# VC8Evrs.net
KiCad netlist of a schematic drawn in EAGLE
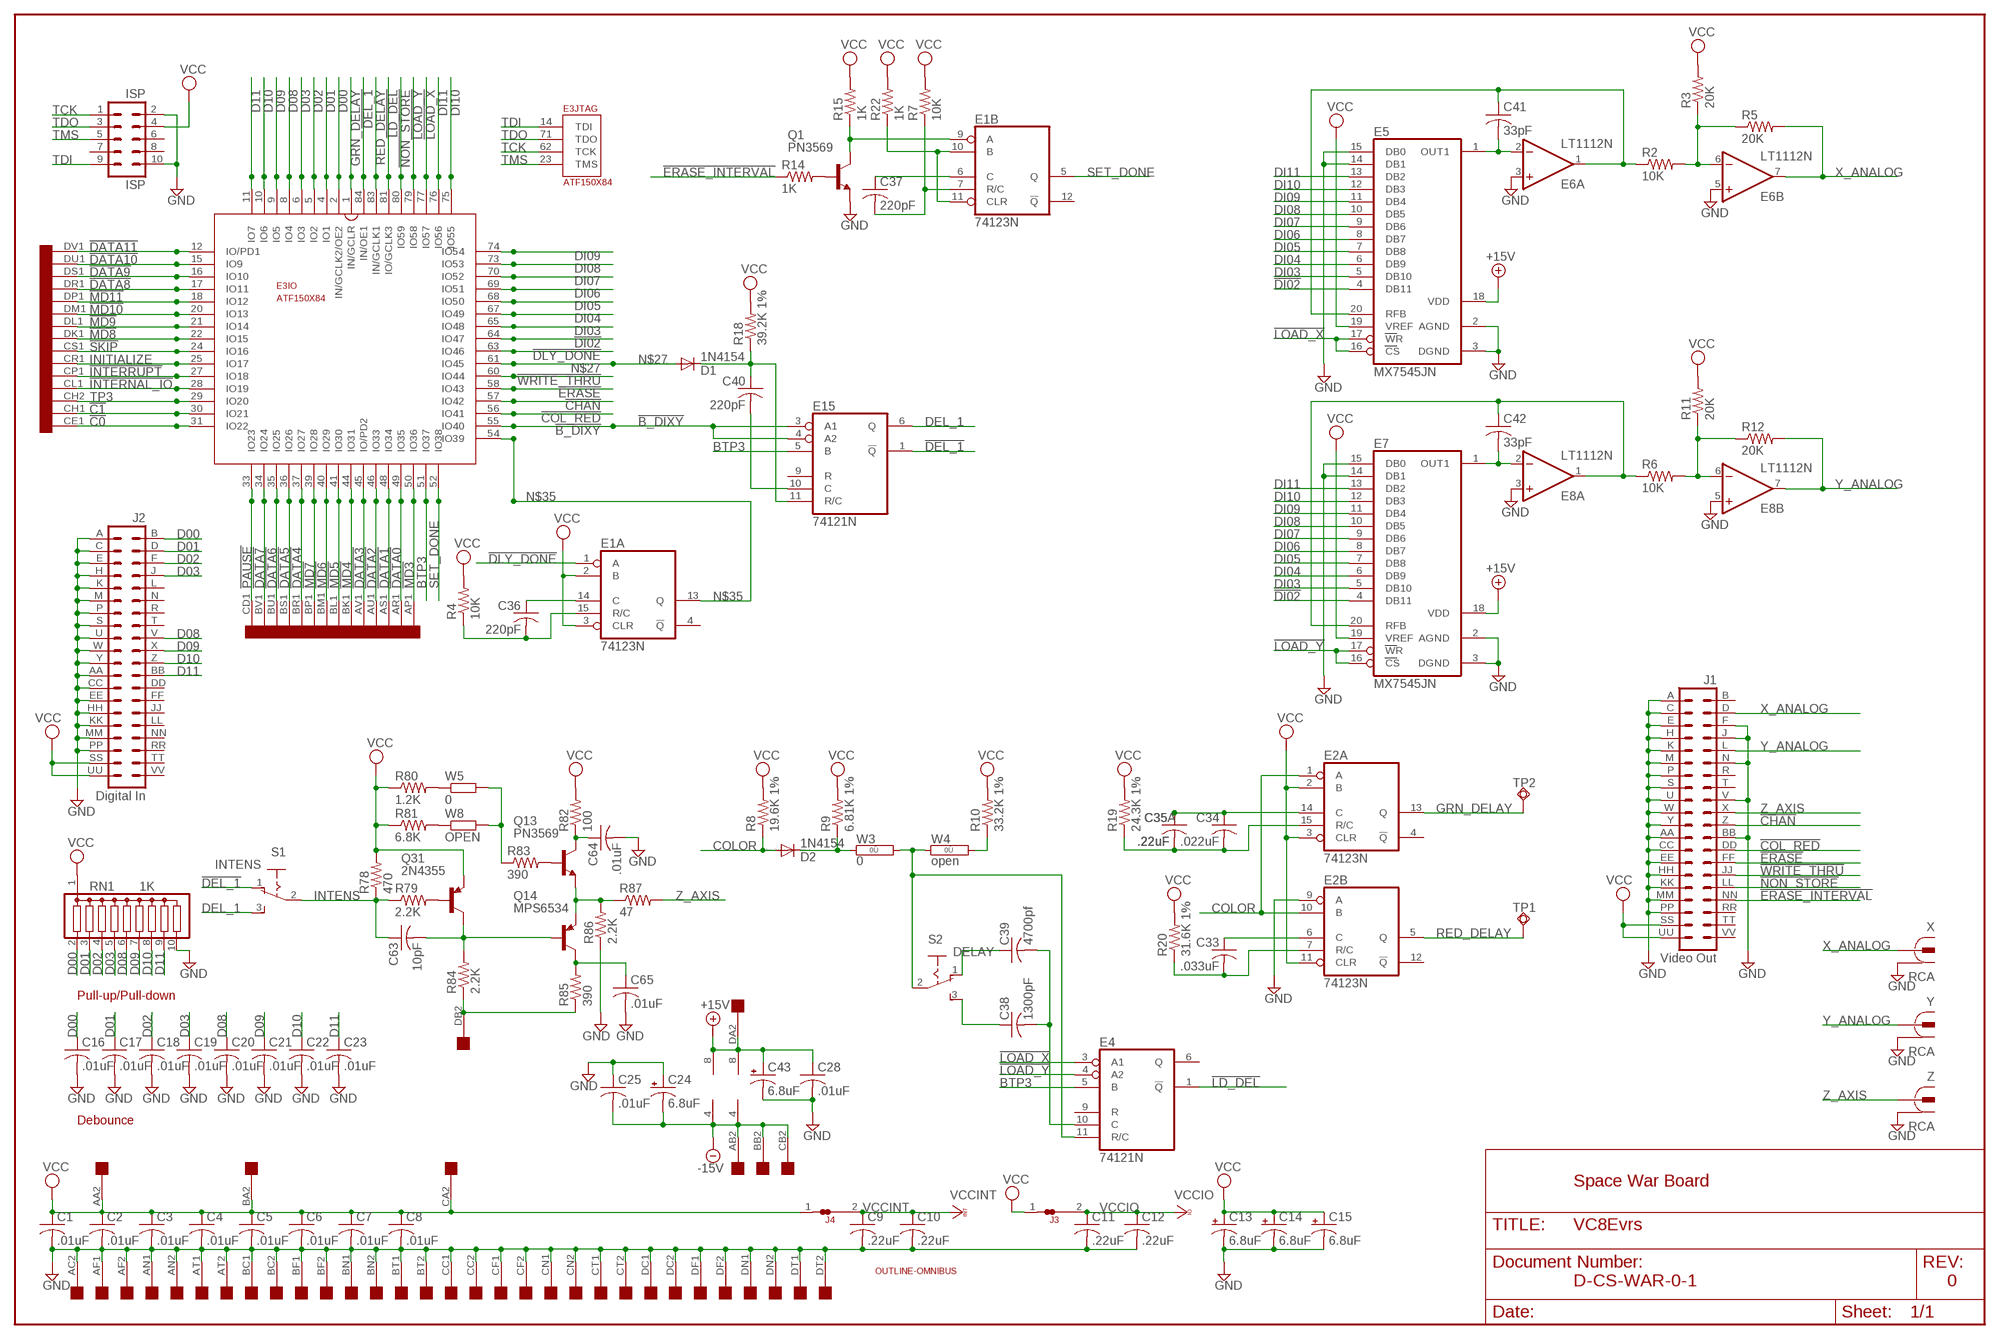
[diagram p0: schematic, sheet 1]

(export (version "E")
  (design (tool "Eeschema 10.0.6"))
  (components
    (comp (ref "C1")
      (value ".01uF")
      (footprint "eagle-import:C063-025X075")
      (libsource (lib "eagle-import") (part "C-US"))
    )
    (comp (ref "C2")
      (value ".01uF")
      (footprint "eagle-import:C063-025X075")
      (libsource (lib "eagle-import") (part "C-US"))
    )
    (comp (ref "C3")
      (value ".01uF")
      (footprint "eagle-import:C063-025X075")
      (libsource (lib "eagle-import") (part "C-US"))
    )
    (comp (ref "C4")
      (value ".01uF")
      (footprint "eagle-import:C063-025X075")
      (libsource (lib "eagle-import") (part "C-US"))
    )
    (comp (ref "C5")
      (value ".01uF")
      (footprint "eagle-import:C063-025X075")
      (libsource (lib "eagle-import") (part "C-US"))
    )
    (comp (ref "C6")
      (value ".01uF")
      (footprint "eagle-import:C063-025X075")
      (libsource (lib "eagle-import") (part "C-US"))
    )
    (comp (ref "C7")
      (value ".01uF")
      (footprint "eagle-import:C063-025X075")
      (libsource (lib "eagle-import") (part "C-US"))
    )
    (comp (ref "C8")
      (value ".01uF")
      (footprint "eagle-import:C063-025X075")
      (libsource (lib "eagle-import") (part "C-US"))
    )
    (comp (ref "C9")
      (value ".22uF")
      (footprint "eagle-import:C063-025X075")
      (libsource (lib "eagle-import") (part "C-US"))
    )
    (comp (ref "C10")
      (value ".22uF")
      (footprint "eagle-import:C063-025X075")
      (libsource (lib "eagle-import") (part "C-US"))
    )
    (comp (ref "C11")
      (value ".22uF")
      (footprint "eagle-import:C063-025X075")
      (libsource (lib "eagle-import") (part "C-US"))
    )
    (comp (ref "C12")
      (value ".22uF")
      (footprint "eagle-import:C063-025X075")
      (libsource (lib "eagle-import") (part "C-US"))
    )
    (comp (ref "C13")
      (value "6.8uF")
      (footprint "eagle-import:E12-8")
      (libsource (lib "eagle-import") (part "CPOL-USE20-8AXIAL"))
    )
    (comp (ref "C14")
      (value "6.8uF")
      (footprint "eagle-import:E12-8")
      (libsource (lib "eagle-import") (part "CPOL-USE20-8AXIAL"))
    )
    (comp (ref "C15")
      (value "6.8uF")
      (footprint "eagle-import:E12-8")
      (libsource (lib "eagle-import") (part "CPOL-USE20-8AXIAL"))
    )
    (comp (ref "C16")
      (value ".01uF")
      (footprint "eagle-import:C063-025X075")
      (libsource (lib "eagle-import") (part "C-US"))
    )
    (comp (ref "C17")
      (value ".01uF")
      (footprint "eagle-import:C063-025X075")
      (libsource (lib "eagle-import") (part "C-US"))
    )
    (comp (ref "C18")
      (value ".01uF")
      (footprint "eagle-import:C063-025X075")
      (libsource (lib "eagle-import") (part "C-US"))
    )
    (comp (ref "C19")
      (value ".01uF")
      (footprint "eagle-import:C063-025X075")
      (libsource (lib "eagle-import") (part "C-US"))
    )
    (comp (ref "C20")
      (value ".01uF")
      (footprint "eagle-import:C063-025X075")
      (libsource (lib "eagle-import") (part "C-US"))
    )
    (comp (ref "C21")
      (value ".01uF")
      (footprint "eagle-import:C063-025X075")
      (libsource (lib "eagle-import") (part "C-US"))
    )
    (comp (ref "C22")
      (value ".01uF")
      (footprint "eagle-import:C063-025X075")
      (libsource (lib "eagle-import") (part "C-US"))
    )
    (comp (ref "C23")
      (value ".01uF")
      (footprint "eagle-import:C063-025X075")
      (libsource (lib "eagle-import") (part "C-US"))
    )
    (comp (ref "C24")
      (value "6.8uF")
      (footprint "eagle-import:E12-8")
      (libsource (lib "eagle-import") (part "CPOL-USE20-8AXIAL"))
    )
    (comp (ref "C25")
      (value ".01uF")
      (footprint "eagle-import:C063-025X075")
      (libsource (lib "eagle-import") (part "C-US"))
    )
    (comp (ref "C28")
      (value ".01uF")
      (footprint "eagle-import:C063-025X075")
      (libsource (lib "eagle-import") (part "C-US"))
    )
    (comp (ref "C33")
      (value ".033uF")
      (footprint "eagle-import:C102-043X133")
      (libsource (lib "eagle-import") (part "C-US102-043X133"))
    )
    (comp (ref "C34")
      (value ".022uF")
      (footprint "eagle-import:C102-043X133")
      (libsource (lib "eagle-import") (part "C-US102-043X133"))
    )
    (comp (ref "C35")
      (value ".22uF")
      (footprint "eagle-import:C050-025X075")
      (libsource (lib "eagle-import") (part "C-US050-025X075"))
    )
    (comp (ref "C35A")
      (value ".22uF")
      (footprint "eagle-import:C102-043X133")
      (libsource (lib "eagle-import") (part "C-US102-043X133"))
    )
    (comp (ref "C36")
      (value "220pF")
      (footprint "eagle-import:C063-025X075")
      (libsource (lib "eagle-import") (part "C-US"))
    )
    (comp (ref "C37")
      (value "220pF")
      (footprint "eagle-import:C063-025X075")
      (libsource (lib "eagle-import") (part "C-US"))
    )
    (comp (ref "C38")
      (value "1300pF")
      (footprint "eagle-import:C150-054X183")
      (libsource (lib "eagle-import") (part "C-US150-054X183"))
    )
    (comp (ref "C39")
      (value "4700pf")
      (footprint "eagle-import:C102-043X133")
      (libsource (lib "eagle-import") (part "C-US102-043X133"))
    )
    (comp (ref "C40")
      (value "220pF")
      (footprint "eagle-import:C063-025X075")
      (libsource (lib "eagle-import") (part "C-US"))
    )
    (comp (ref "C41")
      (value "33pF")
      (footprint "eagle-import:C063-025X075")
      (libsource (lib "eagle-import") (part "C-US"))
    )
    (comp (ref "C42")
      (value "33pF")
      (footprint "eagle-import:C063-025X075")
      (libsource (lib "eagle-import") (part "C-US"))
    )
    (comp (ref "C43")
      (value "6.8uF")
      (footprint "eagle-import:E12-8")
      (libsource (lib "eagle-import") (part "CPOL-USE20-8AXIAL"))
    )
    (comp (ref "C63")
      (value "10pF")
      (footprint "eagle-import:C063-025X075")
      (libsource (lib "eagle-import") (part "C-US"))
    )
    (comp (ref "C64")
      (value ".01uF")
      (footprint "eagle-import:C063-025X075")
      (libsource (lib "eagle-import") (part "C-US"))
    )
    (comp (ref "C65")
      (value ".01uF")
      (footprint "eagle-import:C063-025X075")
      (libsource (lib "eagle-import") (part "C-US"))
    )
    (comp (ref "D1")
      (value "1N4154")
      (footprint "eagle-import:DO35-10")
      (libsource (lib "eagle-import") (part "DIODE-DO35-10"))
    )
    (comp (ref "D2")
      (value "1N4154")
      (footprint "eagle-import:DO35-10")
      (libsource (lib "eagle-import") (part "DIODE-DO35-10"))
    )
    (comp (ref "E1")
      (value "74123N")
      (footprint "eagle-import:DIL16")
      (libsource (lib "eagle-import") (part "74123N"))
    )
    (comp (ref "E2")
      (value "74123N")
      (footprint "eagle-import:DIL16")
      (libsource (lib "eagle-import") (part "74123N"))
    )
    (comp (ref "E3")
      (value "ATF150X84")
      (footprint "eagle-import:S84")
      (libsource (lib "eagle-import") (part "ATF150X84"))
    )
    (comp (ref "E4")
      (value "74121N")
      (footprint "eagle-import:DIL14")
      (libsource (lib "eagle-import") (part "74121N"))
    )
    (comp (ref "E5")
      (value "MX7545JN")
      (footprint "eagle-import:DIL20")
      (fields (field (name "MPN") "MX7545JN+"))
      (libsource (lib "eagle-import") (part "MX7545JN"))
    )
    (comp (ref "E6")
      (value "LT1112N")
      (footprint "eagle-import:DIL08")
      (libsource (lib "eagle-import") (part "1458NLM"))
    )
    (comp (ref "E7")
      (value "MX7545JN")
      (footprint "eagle-import:DIL20")
      (fields (field (name "MPN") "MX7545JN+"))
      (libsource (lib "eagle-import") (part "MX7545JN"))
    )
    (comp (ref "E8")
      (value "LT1112N")
      (footprint "eagle-import:DIL08")
      (libsource (lib "eagle-import") (part "1458NLM"))
    )
    (comp (ref "E15")
      (value "74121N")
      (footprint "eagle-import:DIL14")
      (libsource (lib "eagle-import") (part "74121N"))
    )
    (comp (ref "ISP")
      (value "ISP")
      (footprint "eagle-import:ML10")
      (libsource (lib "eagle-import") (part "ML10"))
    )
    (comp (ref "J1")
      (value "Video Out")
      (footprint "eagle-import:DEC40PINH")
      (libsource (lib "eagle-import") (part "DEC40PINH"))
    )
    (comp (ref "J2")
      (value "Digital In")
      (footprint "eagle-import:DEC40PINH")
      (libsource (lib "eagle-import") (part "DEC40PINH"))
    )
    (comp (ref "J3")
      (value "JUMPER-NC1")
      (footprint "eagle-import:NC1")
      (libsource (lib "eagle-import") (part "JUMPER-NC1"))
    )
    (comp (ref "J4")
      (value "JUMPER-NC1")
      (footprint "eagle-import:NC1")
      (libsource (lib "eagle-import") (part "JUMPER-NC1"))
    )
    (comp (ref "OMNIBUS")
      (value "QUAD")
      (footprint "eagle-import:EDGE-CON8")
      (libsource (lib "eagle-import") (part "QUAD"))
    )
    (comp (ref "Q1")
      (value "PN3569")
      (footprint "eagle-import:TO18-")
      (libsource (lib "eagle-import") (part "-NPN-TO18-"))
    )
    (comp (ref "Q13")
      (value "PN3569")
      (footprint "eagle-import:TO5")
      (libsource (lib "eagle-import") (part "-NPN-TO5"))
    )
    (comp (ref "Q14")
      (value "MPS6534")
      (footprint "eagle-import:TO5")
      (libsource (lib "eagle-import") (part "-PNP-TO5"))
    )
    (comp (ref "Q31")
      (value "2N4355")
      (footprint "eagle-import:TO5")
      (libsource (lib "eagle-import") (part "-PNP-TO5"))
    )
    (comp (ref "R2")
      (value "10K")
      (footprint "eagle-import:0207_10")
      (libsource (lib "eagle-import") (part "R-US_0207/10"))
    )
    (comp (ref "R3")
      (value "20K")
      (footprint "eagle-import:0207_10")
      (libsource (lib "eagle-import") (part "R-US_0207/10"))
    )
    (comp (ref "R4")
      (value "10K")
      (footprint "eagle-import:0207_10")
      (libsource (lib "eagle-import") (part "R-US_0207/10"))
    )
    (comp (ref "R5")
      (value "20K")
      (footprint "eagle-import:0207_10")
      (libsource (lib "eagle-import") (part "R-US_0207/10"))
    )
    (comp (ref "R6")
      (value "10K")
      (footprint "eagle-import:0207_10")
      (libsource (lib "eagle-import") (part "R-US_0207/10"))
    )
    (comp (ref "R7")
      (value "10K")
      (footprint "eagle-import:0207_10")
      (libsource (lib "eagle-import") (part "R-US_0207/10"))
    )
    (comp (ref "R8")
      (value "19.6K 1%")
      (footprint "eagle-import:0207_15")
      (libsource (lib "eagle-import") (part "R-US_0207/15"))
    )
    (comp (ref "R9")
      (value "6.81K 1%")
      (footprint "eagle-import:0207_15")
      (libsource (lib "eagle-import") (part "R-US_0207/15"))
    )
    (comp (ref "R10")
      (value "33.2K 1%")
      (footprint "eagle-import:0207_15")
      (libsource (lib "eagle-import") (part "R-US_0207/15"))
    )
    (comp (ref "R11")
      (value "20K")
      (footprint "eagle-import:0207_10")
      (libsource (lib "eagle-import") (part "R-US_0207/10"))
    )
    (comp (ref "R12")
      (value "20K")
      (footprint "eagle-import:0207_10")
      (libsource (lib "eagle-import") (part "R-US_0207/10"))
    )
    (comp (ref "R14")
      (value "1K")
      (footprint "eagle-import:0207_10")
      (libsource (lib "eagle-import") (part "R-US_0207/10"))
    )
    (comp (ref "R15")
      (value "1K")
      (footprint "eagle-import:0207_10")
      (libsource (lib "eagle-import") (part "R-US_0207/10"))
    )
    (comp (ref "R18")
      (value "39.2K 1%")
      (footprint "eagle-import:0207_15")
      (libsource (lib "eagle-import") (part "R-US_0207/15"))
    )
    (comp (ref "R19")
      (value "24.3K 1%")
      (footprint "eagle-import:0207_15")
      (libsource (lib "eagle-import") (part "R-US_0207/15"))
    )
    (comp (ref "R20")
      (value "31.6K 1%")
      (footprint "eagle-import:0207_15")
      (libsource (lib "eagle-import") (part "R-US_0207/15"))
    )
    (comp (ref "R22")
      (value "1K")
      (footprint "eagle-import:0207_10")
      (libsource (lib "eagle-import") (part "R-US_0207/10"))
    )
    (comp (ref "R78")
      (value "470")
      (footprint "eagle-import:0207_10")
      (libsource (lib "eagle-import") (part "R-US_0207/10"))
    )
    (comp (ref "R79")
      (value "2.2K")
      (footprint "eagle-import:0207_10")
      (libsource (lib "eagle-import") (part "R-US_0207/10"))
    )
    (comp (ref "R80")
      (value "1.2K")
      (footprint "eagle-import:0207_10")
      (libsource (lib "eagle-import") (part "R-US_0207/10"))
    )
    (comp (ref "R81")
      (value "6.8K")
      (footprint "eagle-import:0207_10")
      (libsource (lib "eagle-import") (part "R-US_0207/10"))
    )
    (comp (ref "R82")
      (value "100")
      (footprint "eagle-import:0207_10")
      (libsource (lib "eagle-import") (part "R-US_0207/10"))
    )
    (comp (ref "R83")
      (value "390")
      (footprint "eagle-import:0207_10")
      (libsource (lib "eagle-import") (part "R-US_0207/10"))
    )
    (comp (ref "R84")
      (value "2.2K")
      (footprint "eagle-import:0207_10")
      (libsource (lib "eagle-import") (part "R-US_0207/10"))
    )
    (comp (ref "R85")
      (value "390")
      (footprint "eagle-import:0207_10")
      (libsource (lib "eagle-import") (part "R-US_0207/10"))
    )
    (comp (ref "R86")
      (value "2.2K")
      (footprint "eagle-import:0207_10")
      (libsource (lib "eagle-import") (part "R-US_0207/10"))
    )
    (comp (ref "R87")
      (value "47")
      (footprint "eagle-import:0207_10")
      (libsource (lib "eagle-import") (part "R-US_0207/10"))
    )
    (comp (ref "RN1")
      (value "1K")
      (footprint "eagle-import:SIL10")
      (libsource (lib "eagle-import") (part "G09R"))
    )
    (comp (ref "S1")
      (value "INTENS")
      (footprint "eagle-import:M251")
      (libsource (lib "eagle-import") (part "M251"))
    )
    (comp (ref "S2")
      (value "DELAY")
      (footprint "eagle-import:M251")
      (libsource (lib "eagle-import") (part "M251"))
    )
    (comp (ref "TP1")
      (value "TPSQPAD1-17")
      (footprint "eagle-import:P1-17")
      (libsource (lib "eagle-import") (part "TPSQPAD1-17"))
    )
    (comp (ref "TP2")
      (value "TPSQPAD1-17")
      (footprint "eagle-import:P1-17")
      (libsource (lib "eagle-import") (part "TPSQPAD1-17"))
    )
    (comp (ref "U$1")
      (value "OUTLINE-OMNIBUS")
      (footprint "eagle-import:OMNIBUS")
      (libsource (lib "eagle-import") (part "OUTLINE-OMNIBUS"))
    )
    (comp (ref "W3")
      (value "0")
      (footprint "eagle-import:0R_10")
      (libsource (lib "eagle-import") (part "0R"))
    )
    (comp (ref "W4")
      (value "open")
      (footprint "eagle-import:0R_10")
      (libsource (lib "eagle-import") (part "0R"))
    )
    (comp (ref "W5")
      (value "0")
      (footprint "eagle-import:0207_10")
      (libsource (lib "eagle-import") (part "R-EU_0207/10"))
    )
    (comp (ref "W8")
      (value "OPEN")
      (footprint "eagle-import:0207_10")
      (libsource (lib "eagle-import") (part "R-EU_0207/10"))
    )
    (comp (ref "X")
      (value "RCA")
      (footprint "eagle-import:RCA")
      (libsource (lib "eagle-import") (part "RCA"))
    )
    (comp (ref "Y")
      (value "RCA")
      (footprint "eagle-import:RCA")
      (libsource (lib "eagle-import") (part "RCA"))
    )
    (comp (ref "Z")
      (value "RCA")
      (footprint "eagle-import:RCA")
      (libsource (lib "eagle-import") (part "RCA"))
    )
  )
  (nets
    (net (code "1") (name "+15V") (class "Default")
      (node (ref "C28") (pin "1") (pinfunction "1_1") (pintype "passive"))
      (node (ref "C43") (pin "+") (pinfunction "+_+") (pintype "passive"))
      (node (ref "E5") (pin "18") (pinfunction "VDD_18") (pintype "power_in"))
      (node (ref "E6") (pin "8") (pinfunction "V+_8") (pintype "power_in"))
      (node (ref "E7") (pin "18") (pinfunction "VDD_18") (pintype "power_in"))
      (node (ref "E8") (pin "8") (pinfunction "V+_8") (pintype "power_in"))
      (node (ref "OMNIBUS") (pin "DA2") (pinfunction "1_DA2") (pintype "bidirectional"))
    )
    (net (code "2") (name "-15V") (class "Default")
      (node (ref "C24") (pin "-") (pinfunction "-_-") (pintype "passive"))
      (node (ref "C25") (pin "2") (pinfunction "2_2") (pintype "passive"))
      (node (ref "E6") (pin "4") (pinfunction "V-_4") (pintype "power_in"))
      (node (ref "E8") (pin "4") (pinfunction "V-_4") (pintype "power_in"))
      (node (ref "OMNIBUS") (pin "AB2") (pinfunction "1_AB2") (pintype "bidirectional"))
      (node (ref "OMNIBUS") (pin "BB2") (pinfunction "1_BB2") (pintype "bidirectional"))
      (node (ref "OMNIBUS") (pin "CB2") (pinfunction "1_CB2") (pintype "bidirectional"))
    )
    (net (code "3") (name "/BTP3") (class "Default")
      (node (ref "E15") (pin "5") (pinfunction "B_5") (pintype "input"))
      (node (ref "E3") (pin "51") (pinfunction "IO37_51") (pintype "bidirectional"))
      (node (ref "E4") (pin "5") (pinfunction "B_5") (pintype "input"))
    )
    (net (code "4") (name "/COLOR") (class "Default")
      (node (ref "D2") (pin "A") (pinfunction "A_A") (pintype "passive"))
      (node (ref "E2") (pin "1") (pinfunction "A_1") (pintype "input"))
      (node (ref "E2") (pin "10") (pinfunction "B_10") (pintype "input"))
      (node (ref "R8") (pin "1") (pinfunction "1_1") (pintype "passive"))
    )
    (net (code "5") (name "/D00") (class "Default")
      (node (ref "C16") (pin "1") (pinfunction "1_1") (pintype "passive"))
      (node (ref "E3") (pin "2") (pinfunction "IN/GCLK2/OE2_2") (pintype "input"))
      (node (ref "J2") (pin "B") (pinfunction "2_B") (pintype "bidirectional"))
      (node (ref "RN1") (pin "2") (pinfunction "2_2") (pintype "passive"))
    )
    (net (code "6") (name "/D01") (class "Default")
      (node (ref "C17") (pin "1") (pinfunction "1_1") (pintype "passive"))
      (node (ref "E3") (pin "4") (pinfunction "IO1_4") (pintype "bidirectional"))
      (node (ref "J2") (pin "D") (pinfunction "4_D") (pintype "bidirectional"))
      (node (ref "RN1") (pin "3") (pinfunction "3_3") (pintype "passive"))
    )
    (net (code "7") (name "/D02") (class "Default")
      (node (ref "C18") (pin "1") (pinfunction "1_1") (pintype "passive"))
      (node (ref "E3") (pin "5") (pinfunction "IO2_5") (pintype "bidirectional"))
      (node (ref "J2") (pin "F") (pinfunction "6_F") (pintype "bidirectional"))
      (node (ref "RN1") (pin "4") (pinfunction "4_4") (pintype "passive"))
    )
    (net (code "8") (name "/D03") (class "Default")
      (node (ref "C19") (pin "1") (pinfunction "1_1") (pintype "passive"))
      (node (ref "E3") (pin "6") (pinfunction "IO3_6") (pintype "bidirectional"))
      (node (ref "J2") (pin "J") (pinfunction "8_J") (pintype "bidirectional"))
      (node (ref "RN1") (pin "5") (pinfunction "5_5") (pintype "passive"))
    )
    (net (code "9") (name "/D08") (class "Default")
      (node (ref "C20") (pin "1") (pinfunction "1_1") (pintype "passive"))
      (node (ref "E3") (pin "8") (pinfunction "IO4_8") (pintype "bidirectional"))
      (node (ref "J2") (pin "V") (pinfunction "18_V") (pintype "bidirectional"))
      (node (ref "RN1") (pin "6") (pinfunction "6_6") (pintype "passive"))
    )
    (net (code "10") (name "/D09") (class "Default")
      (node (ref "C21") (pin "1") (pinfunction "1_1") (pintype "passive"))
      (node (ref "E3") (pin "9") (pinfunction "IO5_9") (pintype "bidirectional"))
      (node (ref "J2") (pin "X") (pinfunction "20_X") (pintype "bidirectional"))
      (node (ref "RN1") (pin "7") (pinfunction "7_7") (pintype "passive"))
    )
    (net (code "11") (name "/D10") (class "Default")
      (node (ref "C22") (pin "1") (pinfunction "1_1") (pintype "passive"))
      (node (ref "E3") (pin "10") (pinfunction "IO6_10") (pintype "bidirectional"))
      (node (ref "J2") (pin "Z") (pinfunction "22_Z") (pintype "bidirectional"))
      (node (ref "RN1") (pin "8") (pinfunction "8_8") (pintype "passive"))
    )
    (net (code "12") (name "/D11") (class "Default")
      (node (ref "C23") (pin "1") (pinfunction "1_1") (pintype "passive"))
      (node (ref "E3") (pin "11") (pinfunction "IO7_11") (pintype "bidirectional"))
      (node (ref "J2") (pin "BB") (pinfunction "24_BB") (pintype "bidirectional"))
      (node (ref "RN1") (pin "9") (pinfunction "9_9") (pintype "passive"))
    )
    (net (code "13") (name "/DEL_1") (class "Default")
      (node (ref "E15") (pin "6") (pinfunction "Q_6") (pintype "output"))
      (node (ref "S1") (pin "3") (pinfunction "S_3") (pintype "passive"))
    )
    (net (code "14") (name "/DI03") (class "Default")
      (node (ref "E3") (pin "65") (pinfunction "IO48_65") (pintype "bidirectional"))
      (node (ref "E5") (pin "5") (pinfunction "DB10_5") (pintype "input"))
      (node (ref "E7") (pin "5") (pinfunction "DB10_5") (pintype "input"))
    )
    (net (code "15") (name "/DI04") (class "Default")
      (node (ref "E3") (pin "67") (pinfunction "IO49_67") (pintype "bidirectional"))
      (node (ref "E5") (pin "6") (pinfunction "DB9_6") (pintype "input"))
      (node (ref "E7") (pin "6") (pinfunction "DB9_6") (pintype "input"))
    )
    (net (code "16") (name "/DI05") (class "Default")
      (node (ref "E3") (pin "68") (pinfunction "IO50_68") (pintype "bidirectional"))
      (node (ref "E5") (pin "7") (pinfunction "DB8_7") (pintype "input"))
      (node (ref "E7") (pin "7") (pinfunction "DB8_7") (pintype "input"))
    )
    (net (code "17") (name "/DI06") (class "Default")
      (node (ref "E3") (pin "69") (pinfunction "IO51_69") (pintype "bidirectional"))
      (node (ref "E5") (pin "8") (pinfunction "DB7_8") (pintype "input"))
      (node (ref "E7") (pin "8") (pinfunction "DB7_8") (pintype "input"))
    )
    (net (code "18") (name "/DI07") (class "Default")
      (node (ref "E3") (pin "70") (pinfunction "IO52_70") (pintype "bidirectional"))
      (node (ref "E5") (pin "9") (pinfunction "DB6_9") (pintype "input"))
      (node (ref "E7") (pin "9") (pinfunction "DB6_9") (pintype "input"))
    )
    (net (code "19") (name "/DI08") (class "Default")
      (node (ref "E3") (pin "73") (pinfunction "IO53_73") (pintype "bidirectional"))
      (node (ref "E5") (pin "10") (pinfunction "DB5_10") (pintype "input"))
      (node (ref "E7") (pin "10") (pinfunction "DB5_10") (pintype "input"))
    )
    (net (code "20") (name "/DI09") (class "Default")
      (node (ref "E3") (pin "74") (pinfunction "IO54_74") (pintype "bidirectional"))
      (node (ref "E5") (pin "11") (pinfunction "DB4_11") (pintype "input"))
      (node (ref "E7") (pin "11") (pinfunction "DB4_11") (pintype "input"))
    )
    (net (code "21") (name "/DI10") (class "Default")
      (node (ref "E3") (pin "75") (pinfunction "IO55_75") (pintype "bidirectional"))
      (node (ref "E5") (pin "12") (pinfunction "DB3_12") (pintype "input"))
      (node (ref "E7") (pin "12") (pinfunction "DB3_12") (pintype "input"))
    )
    (net (code "22") (name "/DI11") (class "Default")
      (node (ref "E3") (pin "76") (pinfunction "IO56_76") (pintype "bidirectional"))
      (node (ref "E5") (pin "13") (pinfunction "DB2_13") (pintype "input"))
      (node (ref "E7") (pin "13") (pinfunction "DB2_13") (pintype "input"))
    )
    (net (code "23") (name "/GRN_DELAY") (class "Default")
      (node (ref "E2") (pin "13") (pinfunction "Q_13") (pintype "output"))
      (node (ref "E3") (pin "1") (pinfunction "IN/GCLR_1") (pintype "input"))
      (node (ref "TP2") (pin "TP") (pinfunction "TP_TP") (pintype "input"))
    )
    (net (code "24") (name "/INITIALIZE") (class "Default")
      (node (ref "E3") (pin "25") (pinfunction "IO17_25") (pintype "bidirectional"))
      (node (ref "OMNIBUS") (pin "CR1") (pinfunction "1_CR1") (pintype "bidirectional"))
    )
    (net (code "25") (name "/INTENS") (class "Default")
      (node (ref "C63") (pin "1") (pinfunction "1_1") (pintype "passive"))
      (node (ref "R78") (pin "1") (pinfunction "1_1") (pintype "passive"))
      (node (ref "R79") (pin "1") (pinfunction "1_1") (pintype "passive"))
      (node (ref "S1") (pin "2") (pinfunction "P_2") (pintype "passive"))
    )
    (net (code "26") (name "/N$27") (class "Default")
      (node (ref "D1") (pin "A") (pinfunction "A_A") (pintype "passive"))
      (node (ref "E3") (pin "61") (pinfunction "IO45_61") (pintype "bidirectional"))
    )
    (net (code "27") (name "/N$35") (class "Default")
      (node (ref "E1") (pin "13") (pinfunction "Q_13") (pintype "output"))
      (node (ref "E3") (pin "54") (pinfunction "IO39_54") (pintype "bidirectional"))
    )
    (net (code "28") (name "/RED_DELAY") (class "Default")
      (node (ref "E2") (pin "5") (pinfunction "Q_5") (pintype "output"))
      (node (ref "E3") (pin "83") (pinfunction "IN/GCLK1_83") (pintype "input"))
      (node (ref "TP1") (pin "TP") (pinfunction "TP_TP") (pintype "input"))
    )
    (net (code "29") (name "/SET_DONE") (class "Default")
      (node (ref "E1") (pin "5") (pinfunction "Q_5") (pintype "output"))
      (node (ref "E3") (pin "52") (pinfunction "IO38_52") (pintype "bidirectional"))
    )
    (net (code "30") (name "/TCK") (class "Default")
      (node (ref "E3") (pin "62") (pinfunction "TCK_62") (pintype "bidirectional"))
      (node (ref "ISP") (pin "1") (pinfunction "1_1") (pintype "passive"))
    )
    (net (code "31") (name "/TDI") (class "Default")
      (node (ref "E3") (pin "14") (pinfunction "TDI_14") (pintype "bidirectional"))
      (node (ref "ISP") (pin "9") (pinfunction "9_9") (pintype "passive"))
    )
    (net (code "32") (name "/TDO") (class "Default")
      (node (ref "E3") (pin "71") (pinfunction "TDO_71") (pintype "bidirectional"))
      (node (ref "ISP") (pin "3") (pinfunction "3_3") (pintype "passive"))
    )
    (net (code "33") (name "/TMS") (class "Default")
      (node (ref "E3") (pin "23") (pinfunction "TMS_23") (pintype "bidirectional"))
      (node (ref "ISP") (pin "5") (pinfunction "5_5") (pintype "passive"))
    )
    (net (code "34") (name "/TP3") (class "Default")
      (node (ref "E3") (pin "29") (pinfunction "IO20_29") (pintype "bidirectional"))
      (node (ref "OMNIBUS") (pin "CH2") (pinfunction "1_CH2") (pintype "bidirectional"))
    )
    (net (code "35") (name "/X_ANALOG") (class "Default")
      (node (ref "E6") (pin "7") (pinfunction "OUT_7") (pintype "output"))
      (node (ref "J1") (pin "D") (pinfunction "4_D") (pintype "bidirectional"))
      (node (ref "R5") (pin "2") (pinfunction "2_2") (pintype "passive"))
      (node (ref "X") (pin "2") (pinfunction "2_2") (pintype "passive"))
    )
    (net (code "36") (name "/Y_ANALOG") (class "Default")
      (node (ref "E8") (pin "7") (pinfunction "OUT_7") (pintype "output"))
      (node (ref "J1") (pin "L") (pinfunction "10_L") (pintype "bidirectional"))
      (node (ref "R12") (pin "2") (pinfunction "2_2") (pintype "passive"))
      (node (ref "Y") (pin "2") (pinfunction "2_2") (pintype "passive"))
    )
    (net (code "37") (name "/Z_AXIS") (class "Default")
      (node (ref "J1") (pin "X") (pinfunction "20_X") (pintype "bidirectional"))
      (node (ref "R87") (pin "2") (pinfunction "2_2") (pintype "passive"))
      (node (ref "Z") (pin "2") (pinfunction "2_2") (pintype "passive"))
    )
    (net (code "38") (name "/~{B_DIXY}") (class "Default")
      (node (ref "E15") (pin "3") (pinfunction "A1_3") (pintype "input"))
      (node (ref "E15") (pin "4") (pinfunction "A2_4") (pintype "input"))
      (node (ref "E3") (pin "55") (pinfunction "IO40_55") (pintype "bidirectional"))
    )
    (net (code "39") (name "/~{C0}") (class "Default")
      (node (ref "E3") (pin "31") (pinfunction "IO22_31") (pintype "bidirectional"))
      (node (ref "OMNIBUS") (pin "CE1") (pinfunction "1_CE1") (pintype "bidirectional"))
    )
    (net (code "40") (name "/~{C1}") (class "Default")
      (node (ref "E3") (pin "30") (pinfunction "IO21_30") (pintype "bidirectional"))
      (node (ref "OMNIBUS") (pin "CH1") (pinfunction "1_CH1") (pintype "bidirectional"))
    )
    (net (code "41") (name "/~{CHAN}") (class "Default")
      (node (ref "E3") (pin "57") (pinfunction "IO42_57") (pintype "bidirectional"))
      (node (ref "J1") (pin "Z") (pinfunction "22_Z") (pintype "bidirectional"))
    )
    (net (code "42") (name "/~{COL_RED}") (class "Default")
      (node (ref "E3") (pin "56") (pinfunction "IO41_56") (pintype "bidirectional"))
      (node (ref "J1") (pin "DD") (pinfunction "26_DD") (pintype "bidirectional"))
    )
    (net (code "43") (name "/~{DATA0}") (class "Default")
      (node (ref "E3") (pin "49") (pinfunction "IO35_49") (pintype "bidirectional"))
      (node (ref "OMNIBUS") (pin "AR1") (pinfunction "1_AR1") (pintype "bidirectional"))
    )
    (net (code "44") (name "/~{DATA1}") (class "Default")
      (node (ref "E3") (pin "48") (pinfunction "IO34_48") (pintype "bidirectional"))
      (node (ref "OMNIBUS") (pin "AS1") (pinfunction "1_AS1") (pintype "bidirectional"))
    )
    (net (code "45") (name "/~{DATA2}") (class "Default")
      (node (ref "E3") (pin "46") (pinfunction "IO33_46") (pintype "bidirectional"))
      (node (ref "OMNIBUS") (pin "AU1") (pinfunction "1_AU1") (pintype "bidirectional"))
    )
    (net (code "46") (name "/~{DATA3}") (class "Default")
      (node (ref "E3") (pin "45") (pinfunction "IO/PD2_45") (pintype "bidirectional"))
      (node (ref "OMNIBUS") (pin "AV1") (pinfunction "1_AV1") (pintype "bidirectional"))
    )
    (net (code "47") (name "/~{DATA4}") (class "Default")
      (node (ref "E3") (pin "37") (pinfunction "IO27_37") (pintype "bidirectional"))
      (node (ref "OMNIBUS") (pin "BR1") (pinfunction "1_BR1") (pintype "bidirectional"))
    )
    (net (code "48") (name "/~{DATA5}") (class "Default")
      (node (ref "E3") (pin "36") (pinfunction "IO26_36") (pintype "bidirectional"))
      (node (ref "OMNIBUS") (pin "BS1") (pinfunction "1_BS1") (pintype "bidirectional"))
    )
    (net (code "49") (name "/~{DATA6}") (class "Default")
      (node (ref "E3") (pin "35") (pinfunction "IO25_35") (pintype "bidirectional"))
      (node (ref "OMNIBUS") (pin "BU1") (pinfunction "1_BU1") (pintype "bidirectional"))
    )
    (net (code "50") (name "/~{DATA7}") (class "Default")
      (node (ref "E3") (pin "34") (pinfunction "IO24_34") (pintype "bidirectional"))
      (node (ref "OMNIBUS") (pin "BV1") (pinfunction "1_BV1") (pintype "bidirectional"))
    )
    (net (code "51") (name "/~{DATA8}") (class "Default")
      (node (ref "E3") (pin "17") (pinfunction "IO11_17") (pintype "bidirectional"))
      (node (ref "OMNIBUS") (pin "DR1") (pinfunction "1_DR1") (pintype "bidirectional"))
    )
    (net (code "52") (name "/~{DATA9}") (class "Default")
      (node (ref "E3") (pin "16") (pinfunction "IO10_16") (pintype "bidirectional"))
      (node (ref "OMNIBUS") (pin "DS1") (pinfunction "1_DS1") (pintype "bidirectional"))
    )
    (net (code "53") (name "/~{DATA10}") (class "Default")
      (node (ref "E3") (pin "15") (pinfunction "IO9_15") (pintype "bidirectional"))
      (node (ref "OMNIBUS") (pin "DU1") (pinfunction "1_DU1") (pintype "bidirectional"))
    )
    (net (code "54") (name "/~{DATA11}") (class "Default")
      (node (ref "E3") (pin "12") (pinfunction "IO/PD1_12") (pintype "bidirectional"))
      (node (ref "OMNIBUS") (pin "DV1") (pinfunction "1_DV1") (pintype "bidirectional"))
    )
    (net (code "55") (name "/~{DEL_1}") (class "Default")
      (node (ref "E15") (pin "1") (pinfunction "~{Q}_1") (pintype "output"))
      (node (ref "E3") (pin "84") (pinfunction "IN/OE1_84") (pintype "input"))
      (node (ref "S1") (pin "1") (pinfunction "O_1") (pintype "passive"))
    )
    (net (code "56") (name "/~{DI02}") (class "Default")
      (node (ref "E3") (pin "64") (pinfunction "IO47_64") (pintype "bidirectional"))
      (node (ref "E5") (pin "4") (pinfunction "DB11_4") (pintype "input"))
      (node (ref "E7") (pin "4") (pinfunction "DB11_4") (pintype "input"))
    )
    (net (code "57") (name "/~{DLY_DONE}") (class "Default")
      (node (ref "E1") (pin "1") (pinfunction "A_1") (pintype "input"))
      (node (ref "E3") (pin "63") (pinfunction "IO46_63") (pintype "bidirectional"))
    )
    (net (code "58") (name "/~{ERASE_INTERVAL}") (class "Default")
      (node (ref "J1") (pin "NN") (pinfunction "34_NN") (pintype "bidirectional"))
      (node (ref "R14") (pin "1") (pinfunction "1_1") (pintype "passive"))
    )
    (net (code "59") (name "/~{ERASE}") (class "Default")
      (node (ref "E3") (pin "58") (pinfunction "IO43_58") (pintype "bidirectional"))
      (node (ref "J1") (pin "FF") (pinfunction "28_FF") (pintype "bidirectional"))
    )
    (net (code "60") (name "/~{INTERNAL_IO}") (class "Default")
      (node (ref "E3") (pin "28") (pinfunction "IO19_28") (pintype "bidirectional"))
      (node (ref "OMNIBUS") (pin "CL1") (pinfunction "1_CL1") (pintype "bidirectional"))
    )
    (net (code "61") (name "/~{INTERRUPT}") (class "Default")
      (node (ref "E3") (pin "27") (pinfunction "IO18_27") (pintype "bidirectional"))
      (node (ref "OMNIBUS") (pin "CP1") (pinfunction "1_CP1") (pintype "bidirectional"))
    )
    (net (code "62") (name "/~{LD_DEL}") (class "Default")
      (node (ref "E3") (pin "81") (pinfunction "IO/GCLK3_81") (pintype "bidirectional"))
      (node (ref "E4") (pin "1") (pinfunction "~{Q}_1") (pintype "output"))
    )
    (net (code "63") (name "/~{LOAD_X}") (class "Default")
      (node (ref "E3") (pin "77") (pinfunction "IO57_77") (pintype "bidirectional"))
      (node (ref "E4") (pin "3") (pinfunction "A1_3") (pintype "input"))
      (node (ref "E5") (pin "16") (pinfunction "CS_16") (pintype "input"))
      (node (ref "E5") (pin "17") (pinfunction "WR_17") (pintype "input"))
    )
    (net (code "64") (name "/~{LOAD_Y}") (class "Default")
      (node (ref "E3") (pin "79") (pinfunction "IO58_79") (pintype "bidirectional"))
      (node (ref "E4") (pin "4") (pinfunction "A2_4") (pintype "input"))
      (node (ref "E7") (pin "16") (pinfunction "CS_16") (pintype "input"))
      (node (ref "E7") (pin "17") (pinfunction "WR_17") (pintype "input"))
    )
    (net (code "65") (name "/~{MD3}") (class "Default")
      (node (ref "E3") (pin "50") (pinfunction "IO36_50") (pintype "bidirectional"))
      (node (ref "OMNIBUS") (pin "AP1") (pinfunction "1_AP1") (pintype "bidirectional"))
    )
    (net (code "66") (name "/~{MD4}") (class "Default")
      (node (ref "E3") (pin "44") (pinfunction "IO31_44") (pintype "bidirectional"))
      (node (ref "OMNIBUS") (pin "BK1") (pinfunction "1_BK1") (pintype "bidirectional"))
    )
    (net (code "67") (name "/~{MD5}") (class "Default")
      (node (ref "E3") (pin "41") (pinfunction "IO30_41") (pintype "bidirectional"))
      (node (ref "OMNIBUS") (pin "BL1") (pinfunction "1_BL1") (pintype "bidirectional"))
    )
    (net (code "68") (name "/~{MD6}") (class "Default")
      (node (ref "E3") (pin "40") (pinfunction "IO29_40") (pintype "bidirectional"))
      (node (ref "OMNIBUS") (pin "BM1") (pinfunction "1_BM1") (pintype "bidirectional"))
    )
    (net (code "69") (name "/~{MD7}") (class "Default")
      (node (ref "E3") (pin "39") (pinfunction "IO28_39") (pintype "bidirectional"))
      (node (ref "OMNIBUS") (pin "BP1") (pinfunction "1_BP1") (pintype "bidirectional"))
    )
    (net (code "70") (name "/~{MD8}") (class "Default")
      (node (ref "E3") (pin "22") (pinfunction "IO15_22") (pintype "bidirectional"))
      (node (ref "OMNIBUS") (pin "DK1") (pinfunction "1_DK1") (pintype "bidirectional"))
    )
    (net (code "71") (name "/~{MD9}") (class "Default")
      (node (ref "E3") (pin "21") (pinfunction "IO14_21") (pintype "bidirectional"))
      (node (ref "OMNIBUS") (pin "DL1") (pinfunction "1_DL1") (pintype "bidirectional"))
    )
    (net (code "72") (name "/~{MD10}") (class "Default")
      (node (ref "E3") (pin "20") (pinfunction "IO13_20") (pintype "bidirectional"))
      (node (ref "OMNIBUS") (pin "DM1") (pinfunction "1_DM1") (pintype "bidirectional"))
    )
    (net (code "73") (name "/~{MD11}") (class "Default")
      (node (ref "E3") (pin "18") (pinfunction "IO12_18") (pintype "bidirectional"))
      (node (ref "OMNIBUS") (pin "DP1") (pinfunction "1_DP1") (pintype "bidirectional"))
    )
    (net (code "74") (name "/~{NON_STORE}") (class "Default")
      (node (ref "E3") (pin "80") (pinfunction "IO59_80") (pintype "bidirectional"))
      (node (ref "J1") (pin "LL") (pinfunction "32_LL") (pintype "bidirectional"))
    )
    (net (code "75") (name "/~{PAUSE}") (class "Default")
      (node (ref "E3") (pin "33") (pinfunction "IO23_33") (pintype "bidirectional"))
      (node (ref "OMNIBUS") (pin "CD1") (pinfunction "1_CD1") (pintype "bidirectional"))
    )
    (net (code "76") (name "/~{SKIP}") (class "Default")
      (node (ref "E3") (pin "24") (pinfunction "IO16_24") (pintype "bidirectional"))
      (node (ref "OMNIBUS") (pin "CS1") (pinfunction "1_CS1") (pintype "bidirectional"))
    )
    (net (code "77") (name "/~{WRITE_THRU}") (class "Default")
      (node (ref "E3") (pin "60") (pinfunction "IO44_60") (pintype "bidirectional"))
      (node (ref "J1") (pin "JJ") (pinfunction "30_JJ") (pintype "bidirectional"))
    )
    (net (code "78") (name "GND") (class "Default")
      (node (ref "C1") (pin "2") (pinfunction "2_2") (pintype "passive"))
      (node (ref "C10") (pin "2") (pinfunction "2_2") (pintype "passive"))
      (node (ref "C11") (pin "2") (pinfunction "2_2") (pintype "passive"))
      (node (ref "C12") (pin "2") (pinfunction "2_2") (pintype "passive"))
      (node (ref "C13") (pin "-") (pinfunction "-_-") (pintype "passive"))
      (node (ref "C14") (pin "-") (pinfunction "-_-") (pintype "passive"))
      (node (ref "C15") (pin "-") (pinfunction "-_-") (pintype "passive"))
      (node (ref "C16") (pin "2") (pinfunction "2_2") (pintype "passive"))
      (node (ref "C17") (pin "2") (pinfunction "2_2") (pintype "passive"))
      (node (ref "C18") (pin "2") (pinfunction "2_2") (pintype "passive"))
      (node (ref "C19") (pin "2") (pinfunction "2_2") (pintype "passive"))
      (node (ref "C2") (pin "2") (pinfunction "2_2") (pintype "passive"))
      (node (ref "C20") (pin "2") (pinfunction "2_2") (pintype "passive"))
      (node (ref "C21") (pin "2") (pinfunction "2_2") (pintype "passive"))
      (node (ref "C22") (pin "2") (pinfunction "2_2") (pintype "passive"))
      (node (ref "C23") (pin "2") (pinfunction "2_2") (pintype "passive"))
      (node (ref "C24") (pin "+") (pinfunction "+_+") (pintype "passive"))
      (node (ref "C25") (pin "1") (pinfunction "1_1") (pintype "passive"))
      (node (ref "C28") (pin "2") (pinfunction "2_2") (pintype "passive"))
      (node (ref "C3") (pin "2") (pinfunction "2_2") (pintype "passive"))
      (node (ref "C4") (pin "2") (pinfunction "2_2") (pintype "passive"))
      (node (ref "C43") (pin "-") (pinfunction "-_-") (pintype "passive"))
      (node (ref "C5") (pin "2") (pinfunction "2_2") (pintype "passive"))
      (node (ref "C6") (pin "2") (pinfunction "2_2") (pintype "passive"))
      (node (ref "C64") (pin "2") (pinfunction "2_2") (pintype "passive"))
      (node (ref "C65") (pin "2") (pinfunction "2_2") (pintype "passive"))
      (node (ref "C7") (pin "2") (pinfunction "2_2") (pintype "passive"))
      (node (ref "C8") (pin "2") (pinfunction "2_2") (pintype "passive"))
      (node (ref "C9") (pin "2") (pinfunction "2_2") (pintype "passive"))
      (node (ref "E2") (pin "9") (pinfunction "A_9") (pintype "input"))
      (node (ref "E5") (pin "14") (pinfunction "DB1_14") (pintype "input"))
      (node (ref "E5") (pin "15") (pinfunction "DB0_15") (pintype "input"))
      (node (ref "E5") (pin "2") (pinfunction "AGND_2") (pintype "power_in"))
      (node (ref "E5") (pin "3") (pinfunction "DGND_3") (pintype "power_in"))
      (node (ref "E6") (pin "3") (pinfunction "+IN_3") (pintype "input"))
      (node (ref "E6") (pin "5") (pinfunction "+IN_5") (pintype "input"))
      (node (ref "E7") (pin "14") (pinfunction "DB1_14") (pintype "input"))
      (node (ref "E7") (pin "15") (pinfunction "DB0_15") (pintype "input"))
      (node (ref "E7") (pin "2") (pinfunction "AGND_2") (pintype "power_in"))
      (node (ref "E7") (pin "3") (pinfunction "DGND_3") (pintype "power_in"))
      (node (ref "E8") (pin "3") (pinfunction "+IN_3") (pintype "input"))
      (node (ref "E8") (pin "5") (pinfunction "+IN_5") (pintype "input"))
      (node (ref "ISP") (pin "10") (pinfunction "10_10") (pintype "passive"))
      (node (ref "ISP") (pin "2") (pinfunction "2_2") (pintype "passive"))
      (node (ref "J1") (pin "A") (pinfunction "1_A") (pintype "bidirectional"))
      (node (ref "J1") (pin "AA") (pinfunction "23_AA") (pintype "bidirectional"))
      (node (ref "J1") (pin "BB") (pinfunction "24_BB") (pintype "bidirectional"))
      (node (ref "J1") (pin "C") (pinfunction "3_C") (pintype "bidirectional"))
      (node (ref "J1") (pin "CC") (pinfunction "25_CC") (pintype "bidirectional"))
      (node (ref "J1") (pin "E") (pinfunction "5_E") (pintype "bidirectional"))
      (node (ref "J1") (pin "EE") (pinfunction "27_EE") (pintype "bidirectional"))
      (node (ref "J1") (pin "F") (pinfunction "6_F") (pintype "bidirectional"))
      (node (ref "J1") (pin "H") (pinfunction "7_H") (pintype "bidirectional"))
      (node (ref "J1") (pin "HH") (pinfunction "29_HH") (pintype "bidirectional"))
      (node (ref "J1") (pin "J") (pinfunction "8_J") (pintype "bidirectional"))
      (node (ref "J1") (pin "K") (pinfunction "9_K") (pintype "bidirectional"))
      (node (ref "J1") (pin "KK") (pinfunction "31_KK") (pintype "bidirectional"))
      (node (ref "J1") (pin "M") (pinfunction "11_M") (pintype "bidirectional"))
      (node (ref "J1") (pin "MM") (pinfunction "33_MM") (pintype "bidirectional"))
      (node (ref "J1") (pin "N") (pinfunction "12_N") (pintype "bidirectional"))
      (node (ref "J1") (pin "P") (pinfunction "13_P") (pintype "bidirectional"))
      (node (ref "J1") (pin "PP") (pinfunction "35_PP") (pintype "bidirectional"))
      (node (ref "J1") (pin "S") (pinfunction "15_S") (pintype "bidirectional"))
      (node (ref "J1") (pin "U") (pinfunction "17_U") (pintype "bidirectional"))
      (node (ref "J1") (pin "V") (pinfunction "18_V") (pintype "bidirectional"))
      (node (ref "J1") (pin "W") (pinfunction "19_W") (pintype "bidirectional"))
      (node (ref "J1") (pin "Y") (pinfunction "21_Y") (pintype "bidirectional"))
      (node (ref "J2") (pin "A") (pinfunction "1_A") (pintype "bidirectional"))
      (node (ref "J2") (pin "AA") (pinfunction "23_AA") (pintype "bidirectional"))
      (node (ref "J2") (pin "C") (pinfunction "3_C") (pintype "bidirectional"))
      (node (ref "J2") (pin "CC") (pinfunction "25_CC") (pintype "bidirectional"))
      (node (ref "J2") (pin "E") (pinfunction "5_E") (pintype "bidirectional"))
      (node (ref "J2") (pin "EE") (pinfunction "27_EE") (pintype "bidirectional"))
      (node (ref "J2") (pin "H") (pinfunction "7_H") (pintype "bidirectional"))
      (node (ref "J2") (pin "HH") (pinfunction "29_HH") (pintype "bidirectional"))
      (node (ref "J2") (pin "K") (pinfunction "9_K") (pintype "bidirectional"))
      (node (ref "J2") (pin "KK") (pinfunction "31_KK") (pintype "bidirectional"))
      (node (ref "J2") (pin "M") (pinfunction "11_M") (pintype "bidirectional"))
      (node (ref "J2") (pin "MM") (pinfunction "33_MM") (pintype "bidirectional"))
      (node (ref "J2") (pin "P") (pinfunction "13_P") (pintype "bidirectional"))
      (node (ref "J2") (pin "PP") (pinfunction "35_PP") (pintype "bidirectional"))
      (node (ref "J2") (pin "S") (pinfunction "15_S") (pintype "bidirectional"))
      (node (ref "J2") (pin "U") (pinfunction "17_U") (pintype "bidirectional"))
      (node (ref "J2") (pin "W") (pinfunction "19_W") (pintype "bidirectional"))
      (node (ref "J2") (pin "Y") (pinfunction "21_Y") (pintype "bidirectional"))
      (node (ref "OMNIBUS") (pin "AC2") (pinfunction "1_AC2") (pintype "bidirectional"))
      (node (ref "OMNIBUS") (pin "AF1") (pinfunction "1_AF1") (pintype "bidirectional"))
      (node (ref "OMNIBUS") (pin "AF2") (pinfunction "1_AF2") (pintype "bidirectional"))
      (node (ref "OMNIBUS") (pin "AN1") (pinfunction "1_AN1") (pintype "bidirectional"))
      (node (ref "OMNIBUS") (pin "AN2") (pinfunction "1_AN2") (pintype "bidirectional"))
      (node (ref "OMNIBUS") (pin "AT1") (pinfunction "1_AT1") (pintype "bidirectional"))
      (node (ref "OMNIBUS") (pin "AT2") (pinfunction "1_AT2") (pintype "bidirectional"))
      (node (ref "OMNIBUS") (pin "BC1") (pinfunction "1_BC1") (pintype "bidirectional"))
      (node (ref "OMNIBUS") (pin "BC2") (pinfunction "1_BC2") (pintype "bidirectional"))
      (node (ref "OMNIBUS") (pin "BF1") (pinfunction "1_BF1") (pintype "bidirectional"))
      (node (ref "OMNIBUS") (pin "BF2") (pinfunction "1_BF2") (pintype "bidirectional"))
      (node (ref "OMNIBUS") (pin "BN1") (pinfunction "1_BN1") (pintype "bidirectional"))
      (node (ref "OMNIBUS") (pin "BN2") (pinfunction "1_BN2") (pintype "bidirectional"))
      (node (ref "OMNIBUS") (pin "BT1") (pinfunction "1_BT1") (pintype "bidirectional"))
      (node (ref "OMNIBUS") (pin "BT2") (pinfunction "1_BT2") (pintype "bidirectional"))
      (node (ref "OMNIBUS") (pin "CC1") (pinfunction "1_CC1") (pintype "bidirectional"))
      (node (ref "OMNIBUS") (pin "CC2") (pinfunction "1_CC2") (pintype "bidirectional"))
      (node (ref "OMNIBUS") (pin "CF1") (pinfunction "1_CF1") (pintype "bidirectional"))
      (node (ref "OMNIBUS") (pin "CF2") (pinfunction "1_CF2") (pintype "bidirectional"))
      (node (ref "OMNIBUS") (pin "CN1") (pinfunction "1_CN1") (pintype "bidirectional"))
      (node (ref "OMNIBUS") (pin "CN2") (pinfunction "1_CN2") (pintype "bidirectional"))
      (node (ref "OMNIBUS") (pin "CT1") (pinfunction "1_CT1") (pintype "bidirectional"))
      (node (ref "OMNIBUS") (pin "CT2") (pinfunction "1_CT2") (pintype "bidirectional"))
      (node (ref "OMNIBUS") (pin "DC1") (pinfunction "1_DC1") (pintype "bidirectional"))
      (node (ref "OMNIBUS") (pin "DC2") (pinfunction "1_DC2") (pintype "bidirectional"))
      (node (ref "OMNIBUS") (pin "DF1") (pinfunction "1_DF1") (pintype "bidirectional"))
      (node (ref "OMNIBUS") (pin "DF2") (pinfunction "1_DF2") (pintype "bidirectional"))
      (node (ref "OMNIBUS") (pin "DN1") (pinfunction "1_DN1") (pintype "bidirectional"))
      (node (ref "OMNIBUS") (pin "DN2") (pinfunction "1_DN2") (pintype "bidirectional"))
      (node (ref "OMNIBUS") (pin "DT1") (pinfunction "1_DT1") (pintype "bidirectional"))
      (node (ref "OMNIBUS") (pin "DT2") (pinfunction "1_DT2") (pintype "bidirectional"))
      (node (ref "Q1") (pin "1") (pinfunction "E_1") (pintype "passive"))
      (node (ref "R86") (pin "1") (pinfunction "1_1") (pintype "passive"))
      (node (ref "RN1") (pin "10") (pinfunction "10_10") (pintype "passive"))
      (node (ref "X") (pin "1") (pinfunction "1_1") (pintype "passive"))
      (node (ref "X") (pin "1@1") (pinfunction "1_1@1") (pintype "passive"))
      (node (ref "X") (pin "1@2") (pinfunction "1_1@2") (pintype "passive"))
      (node (ref "Y") (pin "1") (pinfunction "1_1") (pintype "passive"))
      (node (ref "Y") (pin "1@1") (pinfunction "1_1@1") (pintype "passive"))
      (node (ref "Y") (pin "1@2") (pinfunction "1_1@2") (pintype "passive"))
      (node (ref "Z") (pin "1") (pinfunction "1_1") (pintype "passive"))
      (node (ref "Z") (pin "1@1") (pinfunction "1_1@1") (pintype "passive"))
      (node (ref "Z") (pin "1@2") (pinfunction "1_1@2") (pintype "passive"))
    )
    (net (code "79") (name "Net-(D2-PadC)") (class "Default")
      (node (ref "D2") (pin "C") (pinfunction "C_C") (pintype "passive"))
      (node (ref "R9") (pin "1") (pinfunction "1_1") (pintype "passive"))
      (node (ref "W3") (pin "1") (pinfunction "1_1") (pintype "passive"))
    )
    (net (code "80") (name "Net-(E1A-C)") (class "Default")
      (node (ref "C36") (pin "1") (pinfunction "1_1") (pintype "passive"))
      (node (ref "E1") (pin "14") (pinfunction "C_14") (pintype "input"))
    )
    (net (code "81") (name "Net-(E1A-R{slash}C)") (class "Default")
      (node (ref "C36") (pin "2") (pinfunction "2_2") (pintype "passive"))
      (node (ref "E1") (pin "15") (pinfunction "R/C_15") (pintype "input"))
      (node (ref "R4") (pin "1") (pinfunction "1_1") (pintype "passive"))
    )
    (net (code "82") (name "Net-(E1B-A)") (class "Default")
      (node (ref "E1") (pin "9") (pinfunction "A_9") (pintype "input"))
      (node (ref "Q1") (pin "3") (pinfunction "C_3") (pintype "passive"))
      (node (ref "R15") (pin "1") (pinfunction "1_1") (pintype "passive"))
    )
    (net (code "83") (name "Net-(E1B-B)") (class "Default")
      (node (ref "E1") (pin "10") (pinfunction "B_10") (pintype "input"))
      (node (ref "E1") (pin "11") (pinfunction "CLR_11") (pintype "input"))
      (node (ref "R22") (pin "1") (pinfunction "1_1") (pintype "passive"))
    )
    (net (code "84") (name "Net-(E1B-C)") (class "Default")
      (node (ref "C37") (pin "1") (pinfunction "1_1") (pintype "passive"))
      (node (ref "E1") (pin "6") (pinfunction "C_6") (pintype "input"))
    )
    (net (code "85") (name "Net-(E1B-R{slash}C)") (class "Default")
      (node (ref "C37") (pin "2") (pinfunction "2_2") (pintype "passive"))
      (node (ref "E1") (pin "7") (pinfunction "R/C_7") (pintype "input"))
      (node (ref "R7") (pin "1") (pinfunction "1_1") (pintype "passive"))
    )
    (net (code "86") (name "Net-(E2A-C)") (class "Default")
      (node (ref "C34") (pin "1") (pinfunction "1_1") (pintype "passive"))
      (node (ref "C35") (pin "1") (pinfunction "1_1") (pintype "passive"))
      (node (ref "C35A") (pin "1") (pinfunction "1_1") (pintype "passive"))
      (node (ref "E2") (pin "14") (pinfunction "C_14") (pintype "input"))
    )
    (net (code "87") (name "Net-(E2A-R{slash}C)") (class "Default")
      (node (ref "C34") (pin "2") (pinfunction "2_2") (pintype "passive"))
      (node (ref "C35") (pin "2") (pinfunction "2_2") (pintype "passive"))
      (node (ref "C35A") (pin "2") (pinfunction "2_2") (pintype "passive"))
      (node (ref "E2") (pin "15") (pinfunction "R/C_15") (pintype "input"))
      (node (ref "R19") (pin "1") (pinfunction "1_1") (pintype "passive"))
    )
    (net (code "88") (name "Net-(E2B-C)") (class "Default")
      (node (ref "C33") (pin "1") (pinfunction "1_1") (pintype "passive"))
      (node (ref "E2") (pin "6") (pinfunction "C_6") (pintype "input"))
    )
    (net (code "89") (name "Net-(E2B-R{slash}C)") (class "Default")
      (node (ref "C33") (pin "2") (pinfunction "2_2") (pintype "passive"))
      (node (ref "E2") (pin "7") (pinfunction "R/C_7") (pintype "input"))
      (node (ref "R20") (pin "1") (pinfunction "1_1") (pintype "passive"))
    )
    (net (code "90") (name "Net-(E4A-C)") (class "Default")
      (node (ref "C38") (pin "2") (pinfunction "2_2") (pintype "passive"))
      (node (ref "C39") (pin "2") (pinfunction "2_2") (pintype "passive"))
      (node (ref "E4") (pin "10") (pinfunction "C_10") (pintype "input"))
    )
    (net (code "91") (name "Net-(E4A-R{slash}C)") (class "Default")
      (node (ref "E4") (pin "11") (pinfunction "R/C_11") (pintype "input"))
      (node (ref "S2") (pin "2") (pinfunction "P_2") (pintype "passive"))
      (node (ref "W3") (pin "2") (pinfunction "2_2") (pintype "passive"))
      (node (ref "W4") (pin "1") (pinfunction "1_1") (pintype "passive"))
    )
    (net (code "92") (name "Net-(E5-OUT1)") (class "Default")
      (node (ref "C41") (pin "2") (pinfunction "2_2") (pintype "passive"))
      (node (ref "E5") (pin "1") (pinfunction "OUT1_1") (pintype "output"))
      (node (ref "E6") (pin "2") (pinfunction "-IN_2") (pintype "input"))
    )
    (net (code "93") (name "Net-(E5-RFB)") (class "Default")
      (node (ref "C41") (pin "1") (pinfunction "1_1") (pintype "passive"))
      (node (ref "E5") (pin "20") (pinfunction "RFB_20") (pintype "input"))
      (node (ref "E6") (pin "1") (pinfunction "OUT_1") (pintype "output"))
      (node (ref "R2") (pin "1") (pinfunction "1_1") (pintype "passive"))
    )
    (net (code "94") (name "Net-(E6B--IN)") (class "Default")
      (node (ref "E6") (pin "6") (pinfunction "-IN_6") (pintype "input"))
      (node (ref "R2") (pin "2") (pinfunction "2_2") (pintype "passive"))
      (node (ref "R3") (pin "1") (pinfunction "1_1") (pintype "passive"))
      (node (ref "R5") (pin "1") (pinfunction "1_1") (pintype "passive"))
    )
    (net (code "95") (name "Net-(E7-OUT1)") (class "Default")
      (node (ref "C42") (pin "2") (pinfunction "2_2") (pintype "passive"))
      (node (ref "E7") (pin "1") (pinfunction "OUT1_1") (pintype "output"))
      (node (ref "E8") (pin "2") (pinfunction "-IN_2") (pintype "input"))
    )
    (net (code "96") (name "Net-(E7-RFB)") (class "Default")
      (node (ref "C42") (pin "1") (pinfunction "1_1") (pintype "passive"))
      (node (ref "E7") (pin "20") (pinfunction "RFB_20") (pintype "input"))
      (node (ref "E8") (pin "1") (pinfunction "OUT_1") (pintype "output"))
      (node (ref "R6") (pin "1") (pinfunction "1_1") (pintype "passive"))
    )
    (net (code "97") (name "Net-(E8B--IN)") (class "Default")
      (node (ref "E8") (pin "6") (pinfunction "-IN_6") (pintype "input"))
      (node (ref "R11") (pin "1") (pinfunction "1_1") (pintype "passive"))
      (node (ref "R12") (pin "1") (pinfunction "1_1") (pintype "passive"))
      (node (ref "R6") (pin "2") (pinfunction "2_2") (pintype "passive"))
    )
    (net (code "98") (name "Net-(E15A-C)") (class "Default")
      (node (ref "C40") (pin "2") (pinfunction "2_2") (pintype "passive"))
      (node (ref "E15") (pin "10") (pinfunction "C_10") (pintype "input"))
    )
    (net (code "99") (name "Net-(E15A-R{slash}C)") (class "Default")
      (node (ref "C40") (pin "1") (pinfunction "1_1") (pintype "passive"))
      (node (ref "D1") (pin "C") (pinfunction "C_C") (pintype "passive"))
      (node (ref "E15") (pin "11") (pinfunction "R/C_11") (pintype "input"))
      (node (ref "R18") (pin "1") (pinfunction "1_1") (pintype "passive"))
    )
    (net (code "100") (name "Net-(OMNIBUSDH-1)") (class "Default")
      (node (ref "OMNIBUS") (pin "DB2") (pinfunction "1_DB2") (pintype "bidirectional"))
      (node (ref "R84") (pin "1") (pinfunction "1_1") (pintype "passive"))
      (node (ref "R85") (pin "1") (pinfunction "1_1") (pintype "passive"))
    )
    (net (code "101") (name "Net-(Q1-B)") (class "Default")
      (node (ref "Q1") (pin "2") (pinfunction "B_2") (pintype "passive"))
      (node (ref "R14") (pin "2") (pinfunction "2_2") (pintype "passive"))
    )
    (net (code "102") (name "Net-(Q13-B)") (class "Default")
      (node (ref "Q13") (pin "2") (pinfunction "B_2") (pintype "passive"))
      (node (ref "R83") (pin "2") (pinfunction "2_2") (pintype "passive"))
    )
    (net (code "103") (name "Net-(Q13-C)") (class "Default")
      (node (ref "C64") (pin "1") (pinfunction "1_1") (pintype "passive"))
      (node (ref "Q13") (pin "3") (pinfunction "C_3") (pintype "passive"))
      (node (ref "R82") (pin "1") (pinfunction "1_1") (pintype "passive"))
    )
    (net (code "104") (name "Net-(Q13-E)") (class "Default")
      (node (ref "Q13") (pin "1") (pinfunction "E_1") (pintype "passive"))
      (node (ref "Q14") (pin "1") (pinfunction "E_1") (pintype "passive"))
      (node (ref "R86") (pin "2") (pinfunction "2_2") (pintype "passive"))
      (node (ref "R87") (pin "1") (pinfunction "1_1") (pintype "passive"))
    )
    (net (code "105") (name "Net-(Q14-B)") (class "Default")
      (node (ref "C63") (pin "2") (pinfunction "2_2") (pintype "passive"))
      (node (ref "Q14") (pin "2") (pinfunction "B_2") (pintype "passive"))
      (node (ref "Q31") (pin "3") (pinfunction "C_3") (pintype "passive"))
      (node (ref "R84") (pin "2") (pinfunction "2_2") (pintype "passive"))
    )
    (net (code "106") (name "Net-(Q14-C)") (class "Default")
      (node (ref "C65") (pin "1") (pinfunction "1_1") (pintype "passive"))
      (node (ref "Q14") (pin "3") (pinfunction "C_3") (pintype "passive"))
      (node (ref "R85") (pin "2") (pinfunction "2_2") (pintype "passive"))
    )
    (net (code "107") (name "Net-(Q31-B)") (class "Default")
      (node (ref "Q31") (pin "2") (pinfunction "B_2") (pintype "passive"))
      (node (ref "R79") (pin "2") (pinfunction "2_2") (pintype "passive"))
    )
    (net (code "108") (name "Net-(R10-Pad1)") (class "Default")
      (node (ref "R10") (pin "1") (pinfunction "1_1") (pintype "passive"))
      (node (ref "W4") (pin "2") (pinfunction "2_2") (pintype "passive"))
    )
    (net (code "109") (name "Net-(R80-Pad2)") (class "Default")
      (node (ref "R80") (pin "2") (pinfunction "2_2") (pintype "passive"))
      (node (ref "W5") (pin "1") (pinfunction "1_1") (pintype "passive"))
    )
    (net (code "110") (name "Net-(R81-Pad2)") (class "Default")
      (node (ref "R81") (pin "2") (pinfunction "2_2") (pintype "passive"))
      (node (ref "W8") (pin "1") (pinfunction "1_1") (pintype "passive"))
    )
    (net (code "111") (name "Net-(R83-Pad1)") (class "Default")
      (node (ref "R83") (pin "1") (pinfunction "1_1") (pintype "passive"))
      (node (ref "W5") (pin "2") (pinfunction "2_2") (pintype "passive"))
      (node (ref "W8") (pin "2") (pinfunction "2_2") (pintype "passive"))
    )
    (net (code "112") (name "Net-(S2-O)") (class "Default")
      (node (ref "C39") (pin "1") (pinfunction "1_1") (pintype "passive"))
      (node (ref "S2") (pin "1") (pinfunction "O_1") (pintype "passive"))
    )
    (net (code "113") (name "Net-(S2-S)") (class "Default")
      (node (ref "C38") (pin "1") (pinfunction "1_1") (pintype "passive"))
      (node (ref "S2") (pin "3") (pinfunction "S_3") (pintype "passive"))
    )
    (net (code "114") (name "VCC") (class "Default")
      (node (ref "C1") (pin "1") (pinfunction "1_1") (pintype "passive"))
      (node (ref "C13") (pin "+") (pinfunction "+_+") (pintype "passive"))
      (node (ref "C14") (pin "+") (pinfunction "+_+") (pintype "passive"))
      (node (ref "C15") (pin "+") (pinfunction "+_+") (pintype "passive"))
      (node (ref "C2") (pin "1") (pinfunction "1_1") (pintype "passive"))
      (node (ref "C3") (pin "1") (pinfunction "1_1") (pintype "passive"))
      (node (ref "C4") (pin "1") (pinfunction "1_1") (pintype "passive"))
      (node (ref "C5") (pin "1") (pinfunction "1_1") (pintype "passive"))
      (node (ref "C6") (pin "1") (pinfunction "1_1") (pintype "passive"))
      (node (ref "C7") (pin "1") (pinfunction "1_1") (pintype "passive"))
      (node (ref "C8") (pin "1") (pinfunction "1_1") (pintype "passive"))
      (node (ref "E1") (pin "2") (pinfunction "B_2") (pintype "input"))
      (node (ref "E1") (pin "3") (pinfunction "CLR_3") (pintype "input"))
      (node (ref "E2") (pin "11") (pinfunction "CLR_11") (pintype "input"))
      (node (ref "E2") (pin "2") (pinfunction "B_2") (pintype "input"))
      (node (ref "E2") (pin "3") (pinfunction "CLR_3") (pintype "input"))
      (node (ref "E5") (pin "19") (pinfunction "VREF_19") (pintype "input"))
      (node (ref "E7") (pin "19") (pinfunction "VREF_19") (pintype "input"))
      (node (ref "ISP") (pin "4") (pinfunction "4_4") (pintype "passive"))
      (node (ref "J1") (pin "SS") (pinfunction "37_SS") (pintype "bidirectional"))
      (node (ref "J1") (pin "UU") (pinfunction "39_UU") (pintype "bidirectional"))
      (node (ref "J2") (pin "SS") (pinfunction "37_SS") (pintype "bidirectional"))
      (node (ref "J2") (pin "UU") (pinfunction "39_UU") (pintype "bidirectional"))
      (node (ref "J3") (pin "1") (pinfunction "1_1") (pintype "bidirectional"))
      (node (ref "J4") (pin "1") (pinfunction "1_1") (pintype "bidirectional"))
      (node (ref "OMNIBUS") (pin "AA2") (pinfunction "1_AA2") (pintype "bidirectional"))
      (node (ref "OMNIBUS") (pin "BA2") (pinfunction "1_BA2") (pintype "bidirectional"))
      (node (ref "OMNIBUS") (pin "CA2") (pinfunction "1_CA2") (pintype "bidirectional"))
      (node (ref "Q31") (pin "1") (pinfunction "E_1") (pintype "passive"))
      (node (ref "R10") (pin "2") (pinfunction "2_2") (pintype "passive"))
      (node (ref "R11") (pin "2") (pinfunction "2_2") (pintype "passive"))
      (node (ref "R15") (pin "2") (pinfunction "2_2") (pintype "passive"))
      (node (ref "R18") (pin "2") (pinfunction "2_2") (pintype "passive"))
      (node (ref "R19") (pin "2") (pinfunction "2_2") (pintype "passive"))
      (node (ref "R20") (pin "2") (pinfunction "2_2") (pintype "passive"))
      (node (ref "R22") (pin "2") (pinfunction "2_2") (pintype "passive"))
      (node (ref "R3") (pin "2") (pinfunction "2_2") (pintype "passive"))
      (node (ref "R4") (pin "2") (pinfunction "2_2") (pintype "passive"))
      (node (ref "R7") (pin "2") (pinfunction "2_2") (pintype "passive"))
      (node (ref "R78") (pin "2") (pinfunction "2_2") (pintype "passive"))
      (node (ref "R8") (pin "2") (pinfunction "2_2") (pintype "passive"))
      (node (ref "R80") (pin "1") (pinfunction "1_1") (pintype "passive"))
      (node (ref "R81") (pin "1") (pinfunction "1_1") (pintype "passive"))
      (node (ref "R82") (pin "2") (pinfunction "2_2") (pintype "passive"))
      (node (ref "R9") (pin "2") (pinfunction "2_2") (pintype "passive"))
      (node (ref "RN1") (pin "1") (pinfunction "1_1") (pintype "passive"))
    )
    (net (code "115") (name "VCCINT") (class "Default")
      (node (ref "C10") (pin "1") (pinfunction "1_1") (pintype "passive"))
      (node (ref "C9") (pin "1") (pinfunction "1_1") (pintype "passive"))
      (node (ref "J4") (pin "2") (pinfunction "2_2") (pintype "bidirectional"))
    )
    (net (code "116") (name "VCCIO") (class "Default")
      (node (ref "C11") (pin "1") (pinfunction "1_1") (pintype "passive"))
      (node (ref "C12") (pin "1") (pinfunction "1_1") (pintype "passive"))
      (node (ref "J3") (pin "2") (pinfunction "2_2") (pintype "bidirectional"))
    )
    (net (code "117") (name "unconnected-(E1A-~{Q}-Pad4)") (class "Default")
      (node (ref "E1") (pin "4") (pinfunction "~{Q}_4") (pintype "output"))
    )
    (net (code "118") (name "unconnected-(E1B-~{Q}-Pad12)") (class "Default")
      (node (ref "E1") (pin "12") (pinfunction "~{Q}_12") (pintype "output"))
    )
    (net (code "119") (name "unconnected-(E2A-~{Q}-Pad4)") (class "Default")
      (node (ref "E2") (pin "4") (pinfunction "~{Q}_4") (pintype "output"))
    )
    (net (code "120") (name "unconnected-(E2B-~{Q}-Pad12)") (class "Default")
      (node (ref "E2") (pin "12") (pinfunction "~{Q}_12") (pintype "output"))
    )
    (net (code "121") (name "unconnected-(E4A-Q-Pad6)") (class "Default")
      (node (ref "E4") (pin "6") (pinfunction "Q_6") (pintype "output"))
    )
    (net (code "122") (name "unconnected-(E4A-R-Pad9)") (class "Default")
      (node (ref "E4") (pin "9") (pinfunction "R_9") (pintype "input"))
    )
    (net (code "123") (name "unconnected-(E15A-R-Pad9)") (class "Default")
      (node (ref "E15") (pin "9") (pinfunction "R_9") (pintype "input"))
    )
    (net (code "124") (name "unconnected-(ISP-Pad6)") (class "Default")
      (node (ref "ISP") (pin "6") (pinfunction "6_6") (pintype "passive"))
    )
    (net (code "125") (name "unconnected-(ISP-Pad7)") (class "Default")
      (node (ref "ISP") (pin "7") (pinfunction "7_7") (pintype "passive"))
    )
    (net (code "126") (name "unconnected-(ISP-Pad8)") (class "Default")
      (node (ref "ISP") (pin "8") (pinfunction "8_8") (pintype "passive"))
    )
    (net (code "127") (name "unconnected-(J1-2-PadB)") (class "Default")
      (node (ref "J1") (pin "B") (pinfunction "2_B") (pintype "bidirectional"))
    )
    (net (code "128") (name "unconnected-(J1-14-PadR)") (class "Default")
      (node (ref "J1") (pin "R") (pinfunction "14_R") (pintype "bidirectional"))
    )
    (net (code "129") (name "unconnected-(J1-16-PadT)") (class "Default")
      (node (ref "J1") (pin "T") (pinfunction "16_T") (pintype "bidirectional"))
    )
    (net (code "130") (name "unconnected-(J1-36-PadRR)") (class "Default")
      (node (ref "J1") (pin "RR") (pinfunction "36_RR") (pintype "bidirectional"))
    )
    (net (code "131") (name "unconnected-(J1-38-PadTT)") (class "Default")
      (node (ref "J1") (pin "TT") (pinfunction "38_TT") (pintype "bidirectional"))
    )
    (net (code "132") (name "unconnected-(J1-40-PadVV)") (class "Default")
      (node (ref "J1") (pin "VV") (pinfunction "40_VV") (pintype "bidirectional"))
    )
    (net (code "133") (name "unconnected-(J2-10-PadL)") (class "Default")
      (node (ref "J2") (pin "L") (pinfunction "10_L") (pintype "bidirectional"))
    )
    (net (code "134") (name "unconnected-(J2-12-PadN)") (class "Default")
      (node (ref "J2") (pin "N") (pinfunction "12_N") (pintype "bidirectional"))
    )
    (net (code "135") (name "unconnected-(J2-14-PadR)") (class "Default")
      (node (ref "J2") (pin "R") (pinfunction "14_R") (pintype "bidirectional"))
    )
    (net (code "136") (name "unconnected-(J2-16-PadT)") (class "Default")
      (node (ref "J2") (pin "T") (pinfunction "16_T") (pintype "bidirectional"))
    )
    (net (code "137") (name "unconnected-(J2-26-PadDD)") (class "Default")
      (node (ref "J2") (pin "DD") (pinfunction "26_DD") (pintype "bidirectional"))
    )
    (net (code "138") (name "unconnected-(J2-28-PadFF)") (class "Default")
      (node (ref "J2") (pin "FF") (pinfunction "28_FF") (pintype "bidirectional"))
    )
    (net (code "139") (name "unconnected-(J2-30-PadJJ)") (class "Default")
      (node (ref "J2") (pin "JJ") (pinfunction "30_JJ") (pintype "bidirectional"))
    )
    (net (code "140") (name "unconnected-(J2-32-PadLL)") (class "Default")
      (node (ref "J2") (pin "LL") (pinfunction "32_LL") (pintype "bidirectional"))
    )
    (net (code "141") (name "unconnected-(J2-34-PadNN)") (class "Default")
      (node (ref "J2") (pin "NN") (pinfunction "34_NN") (pintype "bidirectional"))
    )
    (net (code "142") (name "unconnected-(J2-36-PadRR)") (class "Default")
      (node (ref "J2") (pin "RR") (pinfunction "36_RR") (pintype "bidirectional"))
    )
    (net (code "143") (name "unconnected-(J2-38-PadTT)") (class "Default")
      (node (ref "J2") (pin "TT") (pinfunction "38_TT") (pintype "bidirectional"))
    )
    (net (code "144") (name "unconnected-(J2-40-PadVV)") (class "Default")
      (node (ref "J2") (pin "VV") (pinfunction "40_VV") (pintype "bidirectional"))
    )
  )
)
